# MCU_STM32F411CE.net
KiCad netlist of a schematic drawn in Altium Designer
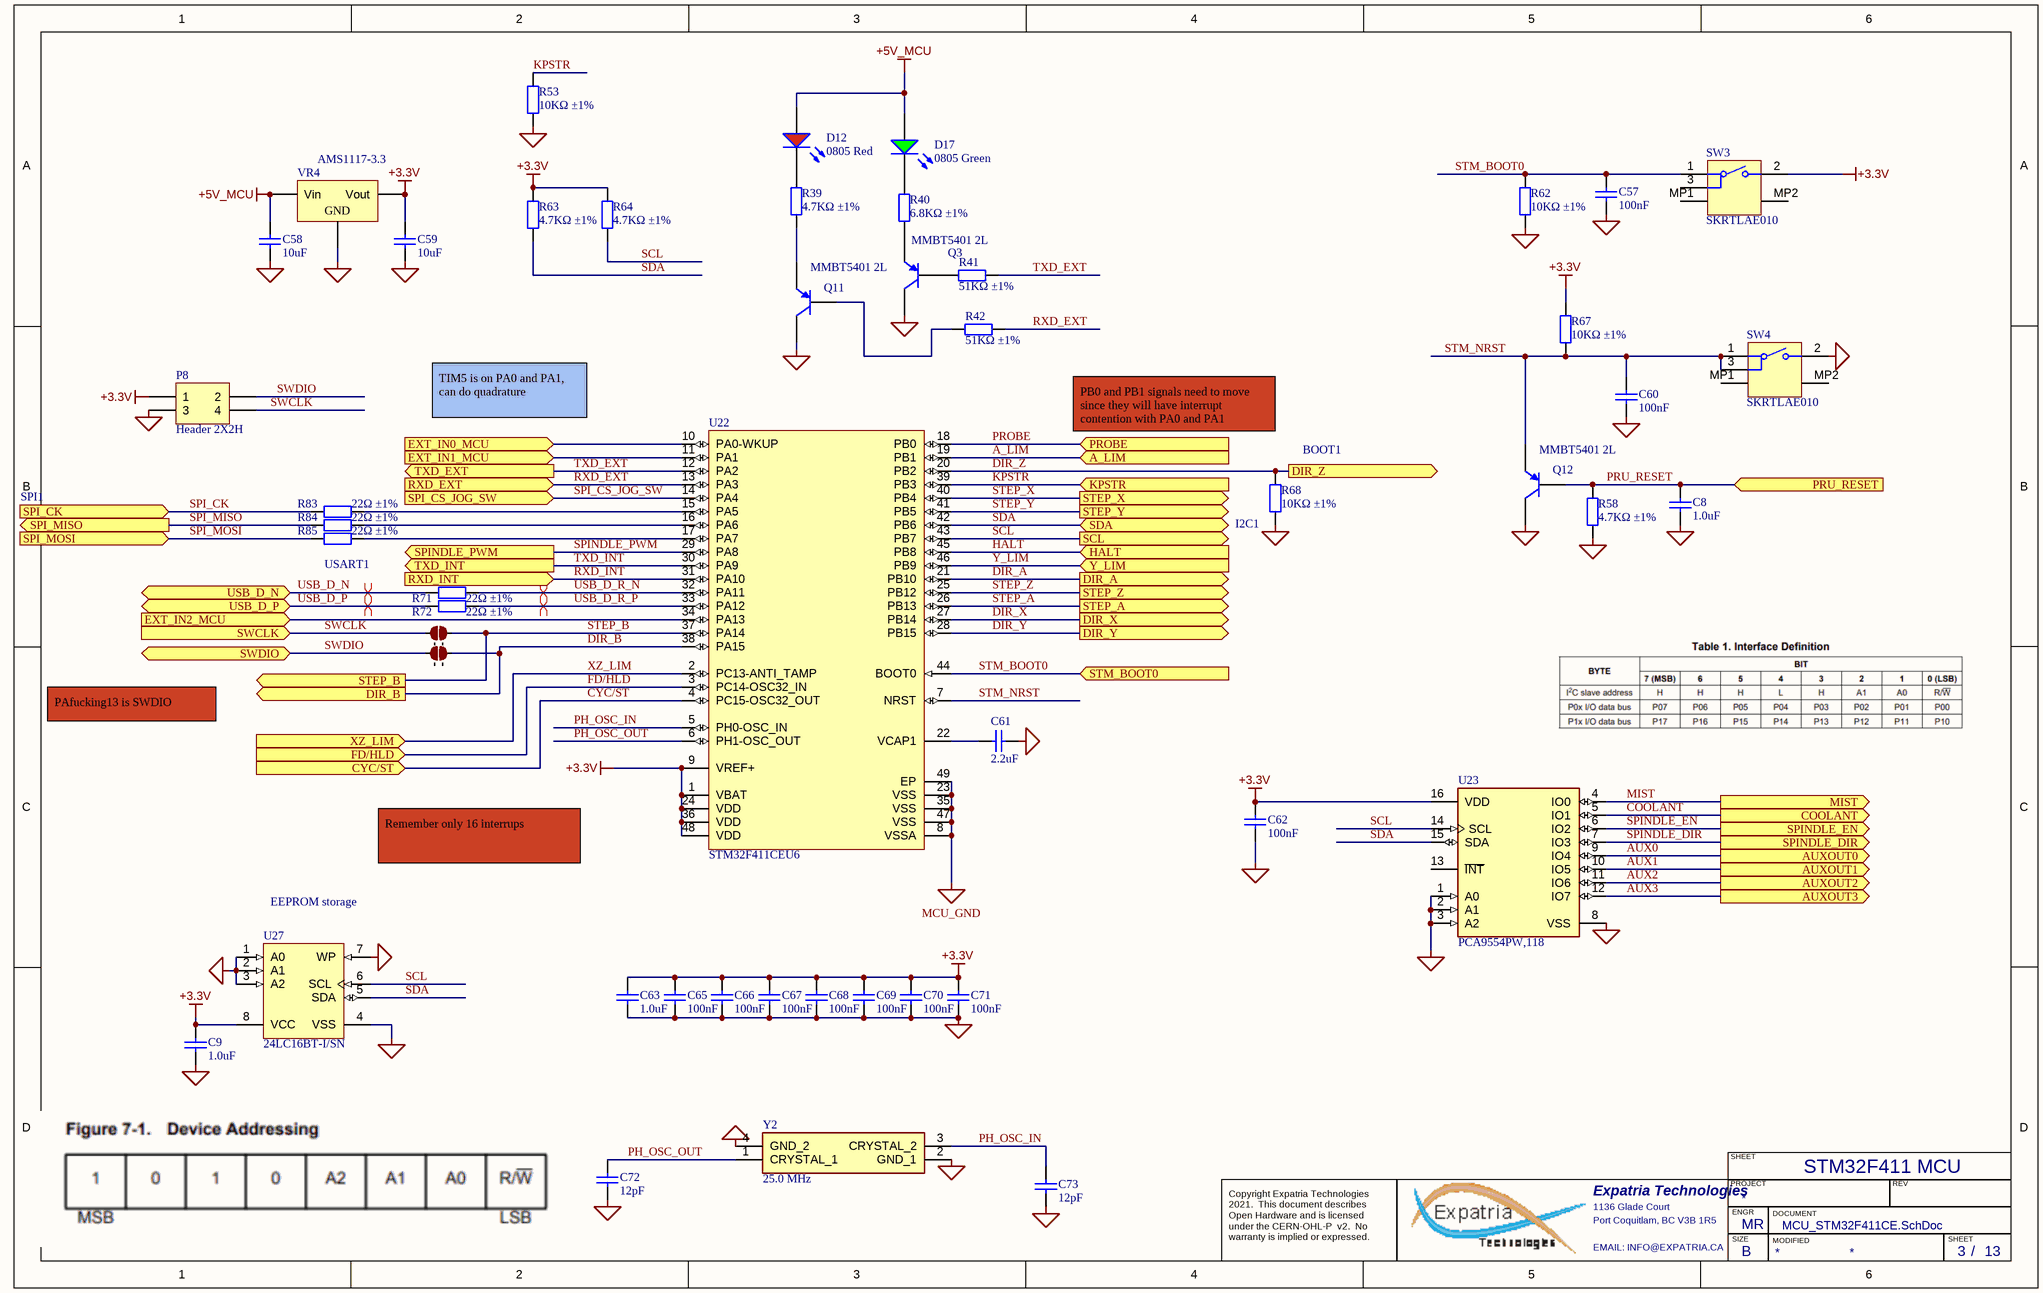
[diagram p0: MCU_STM32F411CE.SchDoc]

(export (version "E")
  (design (tool "Eeschema 10.0.6"))
  (components
    (comp (ref "C8")
      (value "1.0uF")
      (footprint "0402_C")
      (description "Chip capacitor")
      (fields
        (field (name "MANUFACTURER") "Samsung Electro-Mechanics")
        (field (name "PARTNUMBER") "CL05A105KA5NQNC")
      )
      (libsource (lib "Cap") (part "0402 1.0uF (105) 10% 25V"))
    )
    (comp (ref "C9")
      (value "1.0uF")
      (footprint "0402_C")
      (description "Chip capacitor")
      (fields
        (field (name "MANUFACTURER") "Samsung Electro-Mechanics")
        (field (name "PARTNUMBER") "CL05A105KA5NQNC")
      )
      (libsource (lib "Cap") (part "0402 1.0uF (105) 10% 25V"))
    )
    (comp (ref "C57")
      (value "100nF")
      (footprint "0402_C")
      (description "Chip capacitors")
      (fields
        (field (name "MANUFACTURER") "Samsung Electro-Mechanics")
        (field (name "PARTNUMBER") "CL05B104KO5NNNC")
      )
      (libsource (lib "Cap") (part "0402 100nF (104) 10% 16V"))
    )
    (comp (ref "C58")
      (value "10uF")
      (footprint "1206_C")
      (description "Chip capacitors")
      (fields
        (field (name "MANUFACTURER") "Samsung Electro-Mechanics")
        (field (name "PARTNUMBER") "CL31A106KBHNNNE")
      )
      (libsource (lib "Cap") (part "1206 10uF (106) 10% 50V"))
    )
    (comp (ref "C59")
      (value "10uF")
      (footprint "1206_C")
      (description "Chip capacitors")
      (fields
        (field (name "MANUFACTURER") "Samsung Electro-Mechanics")
        (field (name "PARTNUMBER") "CL31A106KBHNNNE")
      )
      (libsource (lib "Cap") (part "1206 10uF (106) 10% 50V"))
    )
    (comp (ref "C60")
      (value "100nF")
      (footprint "0402_C")
      (description "Chip capacitors")
      (fields
        (field (name "MANUFACTURER") "Samsung Electro-Mechanics")
        (field (name "PARTNUMBER") "CL05B104KO5NNNC")
      )
      (libsource (lib "Cap") (part "0402 100nF (104) 10% 16V"))
    )
    (comp (ref "C61")
      (value "2.2uF")
      (footprint "0603_C")
      (description "Chip capacitors")
      (fields
        (field (name "MANUFACTURER") "Samsung Electro-Mechanics")
        (field (name "PARTNUMBER") "CL10A225KO8NNNC")
      )
      (libsource (lib "Cap") (part "0603 2.2uF (225) 10% 16V"))
    )
    (comp (ref "C62")
      (value "100nF")
      (footprint "0402_C")
      (description "Chip capacitors")
      (fields
        (field (name "MANUFACTURER") "Samsung Electro-Mechanics")
        (field (name "PARTNUMBER") "CL05B104KO5NNNC")
      )
      (libsource (lib "Cap") (part "0402 100nF (104) 10% 16V"))
    )
    (comp (ref "C63")
      (value "1.0uF")
      (footprint "0402_C")
      (description "Chip capacitor")
      (fields
        (field (name "MANUFACTURER") "Samsung Electro-Mechanics")
        (field (name "PARTNUMBER") "CL05A105KA5NQNC")
      )
      (libsource (lib "Cap") (part "0402 1.0uF (105) 10% 25V"))
    )
    (comp (ref "C65")
      (value "100nF")
      (footprint "0402_C")
      (description "Chip capacitors")
      (fields
        (field (name "MANUFACTURER") "Samsung Electro-Mechanics")
        (field (name "PARTNUMBER") "CL05B104KO5NNNC")
      )
      (libsource (lib "Cap") (part "0402 100nF (104) 10% 16V"))
    )
    (comp (ref "C66")
      (value "100nF")
      (footprint "0402_C")
      (description "Chip capacitors")
      (fields
        (field (name "MANUFACTURER") "Samsung Electro-Mechanics")
        (field (name "PARTNUMBER") "CL05B104KO5NNNC")
      )
      (libsource (lib "Cap") (part "0402 100nF (104) 10% 16V"))
    )
    (comp (ref "C67")
      (value "100nF")
      (footprint "0402_C")
      (description "Chip capacitors")
      (fields
        (field (name "MANUFACTURER") "Samsung Electro-Mechanics")
        (field (name "PARTNUMBER") "CL05B104KO5NNNC")
      )
      (libsource (lib "Cap") (part "0402 100nF (104) 10% 16V"))
    )
    (comp (ref "C68")
      (value "100nF")
      (footprint "0402_C")
      (description "Chip capacitors")
      (fields
        (field (name "MANUFACTURER") "Samsung Electro-Mechanics")
        (field (name "PARTNUMBER") "CL05B104KO5NNNC")
      )
      (libsource (lib "Cap") (part "0402 100nF (104) 10% 16V"))
    )
    (comp (ref "C69")
      (value "100nF")
      (footprint "0402_C")
      (description "Chip capacitors")
      (fields
        (field (name "MANUFACTURER") "Samsung Electro-Mechanics")
        (field (name "PARTNUMBER") "CL05B104KO5NNNC")
      )
      (libsource (lib "Cap") (part "0402 100nF (104) 10% 16V"))
    )
    (comp (ref "C70")
      (value "100nF")
      (footprint "0402_C")
      (description "Chip capacitors")
      (fields
        (field (name "MANUFACTURER") "Samsung Electro-Mechanics")
        (field (name "PARTNUMBER") "CL05B104KO5NNNC")
      )
      (libsource (lib "Cap") (part "0402 100nF (104) 10% 16V"))
    )
    (comp (ref "C71")
      (value "100nF")
      (footprint "0402_C")
      (description "Chip capacitors")
      (fields
        (field (name "MANUFACTURER") "Samsung Electro-Mechanics")
        (field (name "PARTNUMBER") "CL05B104KO5NNNC")
      )
      (libsource (lib "Cap") (part "0402 100nF (104) 10% 16V"))
    )
    (comp (ref "C72")
      (value "12pF")
      (footprint "0402_C")
      (description "Chip capacitors")
      (fields
        (field (name "MANUFACTURER") "Guangdong Fenghua Advanced Tech")
        (field (name "PARTNUMBER") "0402CG120J500NT")
      )
      (libsource (lib "Cap") (part "0402 12pF (120) 5% 50V"))
    )
    (comp (ref "C73")
      (value "12pF")
      (footprint "0402_C")
      (description "Chip capacitors")
      (fields
        (field (name "MANUFACTURER") "Guangdong Fenghua Advanced Tech")
        (field (name "PARTNUMBER") "0402CG120J500NT")
      )
      (libsource (lib "Cap") (part "0402 12pF (120) 5% 50V"))
    )
    (comp (ref "D12")
      (value "0805 Red")
      (footprint "0805_LED_S1")
      (description "LED")
      (fields
        (field (name "PARTNUMBER") "FC-2012HRK-620D")
        (field (name "MANUFACTURER") "Foshan NationStar Optoelectronics")
      )
      (libsource (lib "LED") (part "0805 LED Red"))
    )
    (comp (ref "D17")
      (value "0805 Green")
      (footprint "0805_LED_S1")
      (description "LED")
      (libsource (lib "LED") (part "0805 LED Green"))
    )
    (comp (ref "J11")
      (value "2 way net solder junction - Normally Open")
      (footprint "2waySolder_NO")
      (libsource (lib "PrintNC_GRBLHAL_Breakout") (part "2waySolderNO"))
    )
    (comp (ref "J13")
      (value "2 way net solder junction - Normally Open")
      (footprint "2waySolder_NO")
      (libsource (lib "PrintNC_GRBLHAL_Breakout") (part "2waySolderNO"))
    )
    (comp (ref "P8")
      (value "Header 2X2H")
      (footprint "HDR2X2H")
      (description "Header, 2-Pin, Dual row, Right Angle")
      (fields (field (name "PUBLISHER") "Altium Limited"))
      (libsource (lib "Miscellaneous Connectors") (part "Header 2X2H"))
    )
    (comp (ref "Q3")
      (value "MMBT5401 2L")
      (footprint "SOT-23(SOT-23-3)")
      (description "三极管")
      (libsource (lib "Transistor_PNP") (part "SOT-23 MMBT5401 2L"))
    )
    (comp (ref "Q11")
      (value "MMBT5401 2L")
      (footprint "SOT-23(SOT-23-3)")
      (description "三极管")
      (libsource (lib "Transistor_PNP") (part "SOT-23 MMBT5401 2L"))
    )
    (comp (ref "Q12")
      (value "MMBT5401 2L")
      (footprint "SOT-23(SOT-23-3)")
      (description "三极管")
      (libsource (lib "Transistor_PNP") (part "SOT-23 MMBT5401 2L"))
    )
    (comp (ref "R39")
      (value "4.7KΩ ±1%")
      (footprint "0402_R")
      (description "Chip resistor")
      (fields (field (name "MANUFACTURER") "Uniroyal Elec") (field (name "PARTNUMBER") "0402WGF4701TCE"))
      (libsource (lib "RES") (part "0402 4.7K (4701) 1%"))
    )
    (comp (ref "R40")
      (value "6.8KΩ ±1%")
      (footprint "0402_R")
      (description "Chip resistor")
      (fields (field (name "MANUFACTURER") "Uniroyal Elec") (field (name "PARTNUMBER") "0402WGF6801TCE"))
      (libsource (lib "RES") (part "0402 6.8K (6801) 1%"))
    )
    (comp (ref "R41")
      (value "51KΩ ±1%")
      (footprint "0402_R")
      (description "Chip resistor")
      (fields (field (name "MANUFACTURER") "Uniroyal Elec") (field (name "PARTNUMBER") "0402WGF5102TCE"))
      (libsource (lib "RES") (part "0402 51K (5102) 1%"))
    )
    (comp (ref "R42")
      (value "51KΩ ±1%")
      (footprint "0402_R")
      (description "Chip resistor")
      (fields (field (name "MANUFACTURER") "Uniroyal Elec") (field (name "PARTNUMBER") "0402WGF5102TCE"))
      (libsource (lib "") (part "0402 51K (5102) 1%_1"))
    )
    (comp (ref "R53")
      (value "10KΩ ±1%")
      (footprint "0402_R")
      (description "Chip resistor")
      (fields (field (name "MANUFACTURER") "Uniroyal Elec") (field (name "PARTNUMBER") "0402WGF1002TCE"))
      (libsource (lib "RES") (part "0402 10K (1002) 1%"))
    )
    (comp (ref "R58")
      (value "4.7KΩ ±1%")
      (footprint "0402_R")
      (description "Chip resistor")
      (fields (field (name "MANUFACTURER") "Uniroyal Elec") (field (name "PARTNUMBER") "0402WGF4701TCE"))
      (libsource (lib "RES") (part "0402 4.7K (4701) 1%"))
    )
    (comp (ref "R62")
      (value "10KΩ ±1%")
      (footprint "0402_R")
      (description "Chip resistor")
      (fields (field (name "MANUFACTURER") "Uniroyal Elec") (field (name "PARTNUMBER") "0402WGF1002TCE"))
      (libsource (lib "") (part "0402 10K (1002) 1%_1"))
    )
    (comp (ref "R63")
      (value "4.7KΩ ±1%")
      (footprint "0402_R")
      (description "Chip resistor")
      (fields (field (name "MANUFACTURER") "Uniroyal Elec") (field (name "PARTNUMBER") "0402WGF4701TCE"))
      (libsource (lib "RES") (part "0402 4.7K (4701) 1%"))
    )
    (comp (ref "R64")
      (value "4.7KΩ ±1%")
      (footprint "0402_R")
      (description "Chip resistor")
      (fields (field (name "MANUFACTURER") "Uniroyal Elec") (field (name "PARTNUMBER") "0402WGF4701TCE"))
      (libsource (lib "RES") (part "0402 4.7K (4701) 1%"))
    )
    (comp (ref "R67")
      (value "10KΩ ±1%")
      (footprint "0402_R")
      (description "Chip resistor")
      (fields (field (name "MANUFACTURER") "Uniroyal Elec") (field (name "PARTNUMBER") "0402WGF1002TCE"))
      (libsource (lib "") (part "0402 10K (1002) 1%_1"))
    )
    (comp (ref "R68")
      (value "10KΩ ±1%")
      (footprint "0402_R")
      (description "Chip resistor")
      (fields (field (name "MANUFACTURER") "Uniroyal Elec") (field (name "PARTNUMBER") "0402WGF1002TCE"))
      (libsource (lib "RES") (part "0402 10K (1002) 1%"))
    )
    (comp (ref "R71")
      (value "22Ω ±1%")
      (footprint "0402_R")
      (description "Chip resistor")
      (fields (field (name "MANUFACTURER") "Uniroyal Elec") (field (name "PARTNUMBER") "0402WGF220JTCE"))
      (libsource (lib "RES") (part "0402 22R (22R0) 1%"))
    )
    (comp (ref "R72")
      (value "22Ω ±1%")
      (footprint "0402_R")
      (description "Chip resistor")
      (fields (field (name "MANUFACTURER") "Uniroyal Elec") (field (name "PARTNUMBER") "0402WGF220JTCE"))
      (libsource (lib "RES") (part "0402 22R (22R0) 1%"))
    )
    (comp (ref "R83")
      (value "22Ω ±1%")
      (footprint "0402_R")
      (description "Chip resistor")
      (fields (field (name "MANUFACTURER") "Uniroyal Elec") (field (name "PARTNUMBER") "0402WGF220JTCE"))
      (libsource (lib "RES") (part "0402 22R (22R0) 1%"))
    )
    (comp (ref "R84")
      (value "22Ω ±1%")
      (footprint "0402_R")
      (description "Chip resistor")
      (fields (field (name "MANUFACTURER") "Uniroyal Elec") (field (name "PARTNUMBER") "0402WGF220JTCE"))
      (libsource (lib "RES") (part "0402 22R (22R0) 1%"))
    )
    (comp (ref "R85")
      (value "22Ω ±1%")
      (footprint "0402_R")
      (description "Chip resistor")
      (fields (field (name "MANUFACTURER") "Uniroyal Elec") (field (name "PARTNUMBER") "0402WGF220JTCE"))
      (libsource (lib "RES") (part "0402 22R (22R0) 1%"))
    )
    (comp (ref "SW3")
      (value "SKRTLAE010")
      (footprint "ALPS-SKRTLAE010_V")
      (description "Side Push Type, 250 V, -40 to 90 degC, 3-Pin SMD, RoHS, Tape and Reel")
      (fields (field (name "MANUFACTURER") "ALPS"))
      (libsource (lib "Altium Content Vault") (part "SW_SPST-3_A"))
    )
    (comp (ref "SW4")
      (value "SKRTLAE010")
      (footprint "ALPS-SKRTLAE010_V")
      (description "Side Push Type, 250 V, -40 to 90 degC, 3-Pin SMD, RoHS, Tape and Reel")
      (fields (field (name "MANUFACTURER") "ALPS"))
      (libsource (lib "Altium Content Vault") (part "SW_SPST-3_A"))
    )
    (comp (ref "U22")
      (value "STM32F411CEU6")
      (footprint "STM-UFQFPN48_M")
      (libsource (lib "Universal_CNC_Breakout") (part "STM32F411CEU6"))
    )
    (comp (ref "U23")
      (value "PCA9554PW,118")
      (footprint "FP-SOT403-1-IPC_C")
      (description "IC I/O EXPANDER I2C 8B 16TSSOP")
      (libsource (lib "Altium Content Vault") (part "2bce3d90e4631a00c558eefe0ba5f01"))
    )
    (comp (ref "U27")
      (value "24LC16BT-I/SN")
      (footprint "SOIC-SN8_L")
      (description "IC EEPROM 16KBIT I2C 8SOIC")
      (libsource (lib "PrintNC_GRBLHAL_Breakout") (part "MEM-SEEPROM-34AA02-IL8"))
    )
    (comp (ref "VR4")
      (value "AMS1117-3.3")
      (footprint "SOT-223")
      (description "低压差线性稳压(LDO)")
      (libsource (lib "LDO") (part "SOT-223 AMS1117-3.3"))
    )
    (comp (ref "Y2")
      (value "25.0 MHz")
      (footprint "SamacSys:YSX321SL")
      (description "Crystal or Oscillator")
      (fields (field (name "MANUFACTURER_PART_NUMBER") "X322525MSB4SI"))
      (libsource (lib "*") (part "YSX321SL"))
    )
  )
  (nets
    (net (code "1") (name "+3.3V") (class "Default")
      (node (ref "C59") (pin "2") (pinfunction "2_2") (pintype "passive"))
      (node (ref "C62") (pin "2") (pinfunction "2_2") (pintype "passive"))
      (node (ref "C63") (pin "2") (pinfunction "2_2") (pintype "passive"))
      (node (ref "C65") (pin "2") (pinfunction "2_2") (pintype "passive"))
      (node (ref "C66") (pin "2") (pinfunction "2_2") (pintype "passive"))
      (node (ref "C67") (pin "2") (pinfunction "2_2") (pintype "passive"))
      (node (ref "C68") (pin "2") (pinfunction "2_2") (pintype "passive"))
      (node (ref "C69") (pin "2") (pinfunction "2_2") (pintype "passive"))
      (node (ref "C70") (pin "2") (pinfunction "2_2") (pintype "passive"))
      (node (ref "C71") (pin "2") (pinfunction "2_2") (pintype "passive"))
      (node (ref "C9") (pin "2") (pinfunction "2_2") (pintype "passive"))
      (node (ref "P8") (pin "1") (pinfunction "1_1") (pintype "passive"))
      (node (ref "R63") (pin "2") (pinfunction "2_2") (pintype "passive"))
      (node (ref "R64") (pin "2") (pinfunction "2_2") (pintype "passive"))
      (node (ref "R67") (pin "1") (pinfunction "1_1") (pintype "passive"))
      (node (ref "SW3") (pin "2") (pinfunction "2_2") (pintype "passive"))
      (node (ref "U22") (pin "1") (pinfunction "VBAT_1") (pintype "power_in"))
      (node (ref "U22") (pin "24") (pinfunction "VDD_24") (pintype "power_in"))
      (node (ref "U22") (pin "36") (pinfunction "VDD_36") (pintype "power_in"))
      (node (ref "U22") (pin "48") (pinfunction "VDD_48") (pintype "power_in"))
      (node (ref "U22") (pin "9") (pinfunction "VREF+_9") (pintype "power_in"))
      (node (ref "U23") (pin "16") (pinfunction "VDD_16") (pintype "power_in"))
      (node (ref "U27") (pin "8") (pinfunction "VCC_8") (pintype "power_in"))
      (node (ref "VR4") (pin "2") (pinfunction "Vout_2") (pintype "passive"))
    )
    (net (code "2") (name "+5V_MCU") (class "Default")
      (node (ref "C58") (pin "2") (pinfunction "2_2") (pintype "passive"))
      (node (ref "D12") (pin "A") (pinfunction "A_A") (pintype "passive"))
      (node (ref "D17") (pin "A") (pinfunction "A_A") (pintype "passive"))
      (node (ref "VR4") (pin "3") (pinfunction "Vin_3") (pintype "passive"))
    )
    (net (code "3") (name "/AUX0") (class "Default")
      (node (ref "U23") (pin "9") (pinfunction "IO4_9") (pintype "bidirectional"))
    )
    (net (code "4") (name "/AUX1") (class "Default")
      (node (ref "U23") (pin "10") (pinfunction "IO5_10") (pintype "bidirectional"))
    )
    (net (code "5") (name "/AUX2") (class "Default")
      (node (ref "U23") (pin "11") (pinfunction "IO6_11") (pintype "bidirectional"))
    )
    (net (code "6") (name "/AUX3") (class "Default")
      (node (ref "U23") (pin "12") (pinfunction "IO7_12") (pintype "bidirectional"))
    )
    (net (code "7") (name "/A_LIM") (class "Default")
      (node (ref "U22") (pin "19") (pinfunction "PB1_19") (pintype "bidirectional"))
    )
    (net (code "8") (name "/COOLANT") (class "Default")
      (node (ref "U23") (pin "5") (pinfunction "IO1_5") (pintype "bidirectional"))
    )
    (net (code "9") (name "/CYC{slash}ST") (class "Default")
      (node (ref "U22") (pin "4") (pinfunction "PC15-OSC32_OUT_4") (pintype "bidirectional"))
    )
    (net (code "10") (name "/DIR_A") (class "Default")
      (node (ref "U22") (pin "21") (pinfunction "PB10_21") (pintype "bidirectional"))
    )
    (net (code "11") (name "/DIR_B") (class "Default")
      (node (ref "J13") (pin "2") (pinfunction "2_2") (pintype "passive"))
      (node (ref "U22") (pin "38") (pinfunction "PA15_38") (pintype "bidirectional"))
    )
    (net (code "12") (name "/DIR_X") (class "Default")
      (node (ref "U22") (pin "27") (pinfunction "PB14_27") (pintype "bidirectional"))
    )
    (net (code "13") (name "/DIR_Y") (class "Default")
      (node (ref "U22") (pin "28") (pinfunction "PB15_28") (pintype "bidirectional"))
    )
    (net (code "14") (name "/DIR_Z") (class "Default")
      (node (ref "R68") (pin "2") (pinfunction "2_2") (pintype "passive"))
      (node (ref "U22") (pin "20") (pinfunction "PB2_20") (pintype "bidirectional"))
    )
    (net (code "15") (name "/EXT_IN0_MCU") (class "Default")
      (node (ref "U22") (pin "10") (pinfunction "PA0-WKUP_10") (pintype "bidirectional"))
    )
    (net (code "16") (name "/EXT_IN1_MCU") (class "Default")
      (node (ref "U22") (pin "11") (pinfunction "PA1_11") (pintype "bidirectional"))
    )
    (net (code "17") (name "/EXT_IN2_MCU") (class "Default")
      (node (ref "U22") (pin "34") (pinfunction "PA13_34") (pintype "bidirectional"))
    )
    (net (code "18") (name "/FD{slash}HLD") (class "Default")
      (node (ref "U22") (pin "3") (pinfunction "PC14-OSC32_IN_3") (pintype "bidirectional"))
    )
    (net (code "19") (name "/HALT") (class "Default")
      (node (ref "U22") (pin "45") (pinfunction "PB8_45") (pintype "bidirectional"))
    )
    (net (code "20") (name "/KPSTR") (class "Default")
      (node (ref "R53") (pin "2") (pinfunction "2_2") (pintype "passive"))
      (node (ref "U22") (pin "39") (pinfunction "PB3_39") (pintype "bidirectional"))
    )
    (net (code "21") (name "/MIST") (class "Default")
      (node (ref "U23") (pin "4") (pinfunction "IO0_4") (pintype "bidirectional"))
    )
    (net (code "22") (name "/PH_OSC_IN") (class "Default")
      (node (ref "C73") (pin "2") (pinfunction "2_2") (pintype "passive"))
      (node (ref "U22") (pin "5") (pinfunction "PH0-OSC_IN_5") (pintype "bidirectional"))
      (node (ref "Y2") (pin "3") (pinfunction "CRYSTAL_2_3") (pintype "passive"))
    )
    (net (code "23") (name "/PH_OSC_OUT") (class "Default")
      (node (ref "C72") (pin "2") (pinfunction "2_2") (pintype "passive"))
      (node (ref "U22") (pin "6") (pinfunction "PH1-OSC_OUT_6") (pintype "bidirectional"))
      (node (ref "Y2") (pin "1") (pinfunction "CRYSTAL_1_1") (pintype "passive"))
    )
    (net (code "24") (name "/PROBE") (class "Default")
      (node (ref "U22") (pin "18") (pinfunction "PB0_18") (pintype "bidirectional"))
    )
    (net (code "25") (name "/PRU_RESET") (class "Default")
      (node (ref "C8") (pin "2") (pinfunction "2_2") (pintype "passive"))
      (node (ref "Q12") (pin "1") (pinfunction "B_1") (pintype "passive"))
      (node (ref "R58") (pin "2") (pinfunction "2_2") (pintype "passive"))
    )
    (net (code "26") (name "/RXD_EXT") (class "Default")
      (node (ref "R42") (pin "1") (pinfunction "1_1") (pintype "passive"))
      (node (ref "U22") (pin "13") (pinfunction "PA3_13") (pintype "bidirectional"))
    )
    (net (code "27") (name "/RXD_INT") (class "Default")
      (node (ref "U22") (pin "31") (pinfunction "PA10_31") (pintype "bidirectional"))
    )
    (net (code "28") (name "/SCL") (class "Default")
      (node (ref "R64") (pin "1") (pinfunction "1_1") (pintype "passive"))
      (node (ref "U22") (pin "43") (pinfunction "PB7_43") (pintype "bidirectional"))
      (node (ref "U23") (pin "14") (pinfunction "SCL_14") (pintype "input"))
      (node (ref "U27") (pin "6") (pinfunction "SCL_6") (pintype "input"))
    )
    (net (code "29") (name "/SDA") (class "Default")
      (node (ref "R63") (pin "1") (pinfunction "1_1") (pintype "passive"))
      (node (ref "U22") (pin "42") (pinfunction "PB6_42") (pintype "bidirectional"))
      (node (ref "U23") (pin "15") (pinfunction "SDA_15") (pintype "bidirectional"))
      (node (ref "U27") (pin "5") (pinfunction "SDA_5") (pintype "bidirectional"))
    )
    (net (code "30") (name "/SPINDLE_DIR") (class "Default")
      (node (ref "U23") (pin "7") (pinfunction "IO3_7") (pintype "bidirectional"))
    )
    (net (code "31") (name "/SPINDLE_EN") (class "Default")
      (node (ref "U23") (pin "6") (pinfunction "IO2_6") (pintype "bidirectional"))
    )
    (net (code "32") (name "/SPINDLE_PWM") (class "Default")
      (node (ref "U22") (pin "29") (pinfunction "PA8_29") (pintype "bidirectional"))
    )
    (net (code "33") (name "/SPI_CK") (class "Default")
      (node (ref "R83") (pin "2") (pinfunction "2_2") (pintype "passive"))
    )
    (net (code "34") (name "/SPI_CS_JOG_SW") (class "Default")
      (node (ref "U22") (pin "14") (pinfunction "PA4_14") (pintype "bidirectional"))
    )
    (net (code "35") (name "/SPI_MISO") (class "Default")
      (node (ref "R84") (pin "2") (pinfunction "2_2") (pintype "passive"))
    )
    (net (code "36") (name "/SPI_MOSI") (class "Default")
      (node (ref "R85") (pin "2") (pinfunction "2_2") (pintype "passive"))
    )
    (net (code "37") (name "/STEP_A") (class "Default")
      (node (ref "U22") (pin "26") (pinfunction "PB13_26") (pintype "bidirectional"))
    )
    (net (code "38") (name "/STEP_B") (class "Default")
      (node (ref "J11") (pin "2") (pinfunction "2_2") (pintype "passive"))
      (node (ref "U22") (pin "37") (pinfunction "PA14_37") (pintype "bidirectional"))
    )
    (net (code "39") (name "/STEP_X") (class "Default")
      (node (ref "U22") (pin "40") (pinfunction "PB4_40") (pintype "bidirectional"))
    )
    (net (code "40") (name "/STEP_Y") (class "Default")
      (node (ref "U22") (pin "41") (pinfunction "PB5_41") (pintype "bidirectional"))
    )
    (net (code "41") (name "/STEP_Z") (class "Default")
      (node (ref "U22") (pin "25") (pinfunction "PB12_25") (pintype "bidirectional"))
    )
    (net (code "42") (name "/STM_BOOT0") (class "Default")
      (node (ref "C57") (pin "2") (pinfunction "2_2") (pintype "passive"))
      (node (ref "R62") (pin "1") (pinfunction "1_1") (pintype "passive"))
      (node (ref "SW3") (pin "1") (pinfunction "1_1") (pintype "passive"))
      (node (ref "U22") (pin "44") (pinfunction "BOOT0_44") (pintype "input"))
    )
    (net (code "43") (name "/STM_NRST") (class "Default")
      (node (ref "C60") (pin "2") (pinfunction "2_2") (pintype "passive"))
      (node (ref "Q12") (pin "2") (pinfunction "E_2") (pintype "passive"))
      (node (ref "R67") (pin "2") (pinfunction "2_2") (pintype "passive"))
      (node (ref "SW4") (pin "1") (pinfunction "1_1") (pintype "passive"))
      (node (ref "SW4") (pin "3") (pinfunction "3_3") (pintype "passive"))
      (node (ref "U22") (pin "7") (pinfunction "NRST_7") (pintype "bidirectional"))
    )
    (net (code "44") (name "/SWCLK") (class "Default")
      (node (ref "J11") (pin "1") (pinfunction "1_1") (pintype "passive"))
      (node (ref "P8") (pin "4") (pinfunction "4_4") (pintype "passive"))
    )
    (net (code "45") (name "/SWDIO") (class "Default")
      (node (ref "J13") (pin "1") (pinfunction "1_1") (pintype "passive"))
      (node (ref "P8") (pin "2") (pinfunction "2_2") (pintype "passive"))
    )
    (net (code "46") (name "/TXD_EXT") (class "Default")
      (node (ref "R41") (pin "2") (pinfunction "2_2") (pintype "passive"))
      (node (ref "U22") (pin "12") (pinfunction "PA2_12") (pintype "bidirectional"))
    )
    (net (code "47") (name "/TXD_INT") (class "Default")
      (node (ref "U22") (pin "30") (pinfunction "PA9_30") (pintype "bidirectional"))
    )
    (net (code "48") (name "/USB_D_N") (class "Default")
      (node (ref "R71") (pin "2") (pinfunction "2_2") (pintype "passive"))
    )
    (net (code "49") (name "/USB_D_P") (class "Default")
      (node (ref "R72") (pin "2") (pinfunction "2_2") (pintype "passive"))
    )
    (net (code "50") (name "/USB_D_R_N") (class "Default")
      (node (ref "R71") (pin "1") (pinfunction "1_1") (pintype "passive"))
      (node (ref "U22") (pin "32") (pinfunction "PA11_32") (pintype "bidirectional"))
    )
    (net (code "51") (name "/USB_D_R_P") (class "Default")
      (node (ref "R72") (pin "1") (pinfunction "1_1") (pintype "passive"))
      (node (ref "U22") (pin "33") (pinfunction "PA12_33") (pintype "bidirectional"))
    )
    (net (code "52") (name "/XZ_LIM") (class "Default")
      (node (ref "U22") (pin "2") (pinfunction "PC13-ANTI_TAMP_2") (pintype "bidirectional"))
    )
    (net (code "53") (name "/Y_LIM") (class "Default")
      (node (ref "U22") (pin "46") (pinfunction "PB9_46") (pintype "bidirectional"))
    )
    (net (code "54") (name "MCU_GND") (class "Default")
      (node (ref "C57") (pin "1") (pinfunction "1_1") (pintype "passive"))
      (node (ref "C58") (pin "1") (pinfunction "1_1") (pintype "passive"))
      (node (ref "C59") (pin "1") (pinfunction "1_1") (pintype "passive"))
      (node (ref "C60") (pin "1") (pinfunction "1_1") (pintype "passive"))
      (node (ref "C61") (pin "1") (pinfunction "1_1") (pintype "passive"))
      (node (ref "C62") (pin "1") (pinfunction "1_1") (pintype "passive"))
      (node (ref "C63") (pin "1") (pinfunction "1_1") (pintype "passive"))
      (node (ref "C65") (pin "1") (pinfunction "1_1") (pintype "passive"))
      (node (ref "C66") (pin "1") (pinfunction "1_1") (pintype "passive"))
      (node (ref "C67") (pin "1") (pinfunction "1_1") (pintype "passive"))
      (node (ref "C68") (pin "1") (pinfunction "1_1") (pintype "passive"))
      (node (ref "C69") (pin "1") (pinfunction "1_1") (pintype "passive"))
      (node (ref "C70") (pin "1") (pinfunction "1_1") (pintype "passive"))
      (node (ref "C71") (pin "1") (pinfunction "1_1") (pintype "passive"))
      (node (ref "C72") (pin "1") (pinfunction "1_1") (pintype "passive"))
      (node (ref "C73") (pin "1") (pinfunction "1_1") (pintype "passive"))
      (node (ref "C8") (pin "1") (pinfunction "1_1") (pintype "passive"))
      (node (ref "C9") (pin "1") (pinfunction "1_1") (pintype "passive"))
      (node (ref "P8") (pin "3") (pinfunction "3_3") (pintype "passive"))
      (node (ref "Q11") (pin "3") (pinfunction "C_3") (pintype "passive"))
      (node (ref "Q12") (pin "3") (pinfunction "C_3") (pintype "passive"))
      (node (ref "Q3") (pin "3") (pinfunction "C_3") (pintype "passive"))
      (node (ref "R53") (pin "1") (pinfunction "1_1") (pintype "passive"))
      (node (ref "R58") (pin "1") (pinfunction "1_1") (pintype "passive"))
      (node (ref "R62") (pin "2") (pinfunction "2_2") (pintype "passive"))
      (node (ref "R68") (pin "1") (pinfunction "1_1") (pintype "passive"))
      (node (ref "SW4") (pin "2") (pinfunction "2_2") (pintype "passive"))
      (node (ref "U22") (pin "23") (pinfunction "VSS_23") (pintype "power_in"))
      (node (ref "U22") (pin "35") (pinfunction "VSS_35") (pintype "power_in"))
      (node (ref "U22") (pin "47") (pinfunction "VSS_47") (pintype "power_in"))
      (node (ref "U22") (pin "49") (pinfunction "EP_49") (pintype "power_in"))
      (node (ref "U22") (pin "8") (pinfunction "VSSA_8") (pintype "power_in"))
      (node (ref "U23") (pin "1") (pinfunction "A0_1") (pintype "input"))
      (node (ref "U23") (pin "2") (pinfunction "A1_2") (pintype "input"))
      (node (ref "U23") (pin "3") (pinfunction "A2_3") (pintype "input"))
      (node (ref "U23") (pin "8") (pinfunction "VSS_8") (pintype "power_in"))
      (node (ref "U27") (pin "1") (pinfunction "A0_1") (pintype "input"))
      (node (ref "U27") (pin "2") (pinfunction "A1_2") (pintype "input"))
      (node (ref "U27") (pin "3") (pinfunction "A2_3") (pintype "input"))
      (node (ref "U27") (pin "4") (pinfunction "VSS_4") (pintype "power_in"))
      (node (ref "U27") (pin "7") (pinfunction "WP_7") (pintype "input"))
      (node (ref "VR4") (pin "1") (pinfunction "GND_1") (pintype "passive"))
      (node (ref "Y2") (pin "2") (pinfunction "GND_1_2") (pintype "passive"))
      (node (ref "Y2") (pin "4") (pinfunction "GND_2_4") (pintype "passive"))
    )
    (net (code "55") (name "Net-(D12-PadK)") (class "Default")
      (node (ref "D12") (pin "K") (pinfunction "K_K") (pintype "passive"))
      (node (ref "R39") (pin "2") (pinfunction "2_2") (pintype "passive"))
    )
    (net (code "56") (name "Net-(D17-PadK)") (class "Default")
      (node (ref "D17") (pin "K") (pinfunction "K_K") (pintype "passive"))
      (node (ref "R40") (pin "2") (pinfunction "2_2") (pintype "passive"))
    )
    (net (code "57") (name "Net-(Q3-B)") (class "Default")
      (node (ref "Q3") (pin "1") (pinfunction "B_1") (pintype "passive"))
      (node (ref "R41") (pin "1") (pinfunction "1_1") (pintype "passive"))
    )
    (net (code "58") (name "Net-(Q3-E)") (class "Default")
      (node (ref "Q3") (pin "2") (pinfunction "E_2") (pintype "passive"))
      (node (ref "R40") (pin "1") (pinfunction "1_1") (pintype "passive"))
    )
    (net (code "59") (name "Net-(Q11-B)") (class "Default")
      (node (ref "Q11") (pin "1") (pinfunction "B_1") (pintype "passive"))
      (node (ref "R42") (pin "2") (pinfunction "2_2") (pintype "passive"))
    )
    (net (code "60") (name "Net-(Q11-E)") (class "Default")
      (node (ref "Q11") (pin "2") (pinfunction "E_2") (pintype "passive"))
      (node (ref "R39") (pin "1") (pinfunction "1_1") (pintype "passive"))
    )
    (net (code "61") (name "Net-(U22-PA5)") (class "Default")
      (node (ref "R83") (pin "1") (pinfunction "1_1") (pintype "passive"))
      (node (ref "U22") (pin "15") (pinfunction "PA5_15") (pintype "bidirectional"))
    )
    (net (code "62") (name "Net-(U22-PA6)") (class "Default")
      (node (ref "R84") (pin "1") (pinfunction "1_1") (pintype "passive"))
      (node (ref "U22") (pin "16") (pinfunction "PA6_16") (pintype "bidirectional"))
    )
    (net (code "63") (name "Net-(U22-PA7)") (class "Default")
      (node (ref "R85") (pin "1") (pinfunction "1_1") (pintype "passive"))
      (node (ref "U22") (pin "17") (pinfunction "PA7_17") (pintype "bidirectional"))
    )
    (net (code "64") (name "Net-(U22-VCAP1)") (class "Default")
      (node (ref "C61") (pin "2") (pinfunction "2_2") (pintype "passive"))
      (node (ref "U22") (pin "22") (pinfunction "VCAP1_22") (pintype "passive"))
    )
    (net (code "65") (name "unconnected-(SW3-Pad3)") (class "Default")
      (node (ref "SW3") (pin "3") (pinfunction "3_3") (pintype "passive"))
    )
    (net (code "66") (name "unconnected-(SW3-PadMP1)") (class "Default")
      (node (ref "SW3") (pin "MP1") (pinfunction "MP1_MP1") (pintype "passive"))
    )
    (net (code "67") (name "unconnected-(SW3-PadMP2)") (class "Default")
      (node (ref "SW3") (pin "MP2") (pinfunction "MP2_MP2") (pintype "passive"))
    )
    (net (code "68") (name "unconnected-(SW4-PadMP1)") (class "Default")
      (node (ref "SW4") (pin "MP1") (pinfunction "MP1_MP1") (pintype "passive"))
    )
    (net (code "69") (name "unconnected-(SW4-PadMP2)") (class "Default")
      (node (ref "SW4") (pin "MP2") (pinfunction "MP2_MP2") (pintype "passive"))
    )
    (net (code "70") (name "unconnected-(U23-~{INT}-Pad13)") (class "Default")
      (node (ref "U23") (pin "13") (pinfunction "~{INT}_13") (pintype "open_collector"))
    )
  )
)
